# 18650_charge.net
KiCad netlist of a schematic drawn in Altium Designer
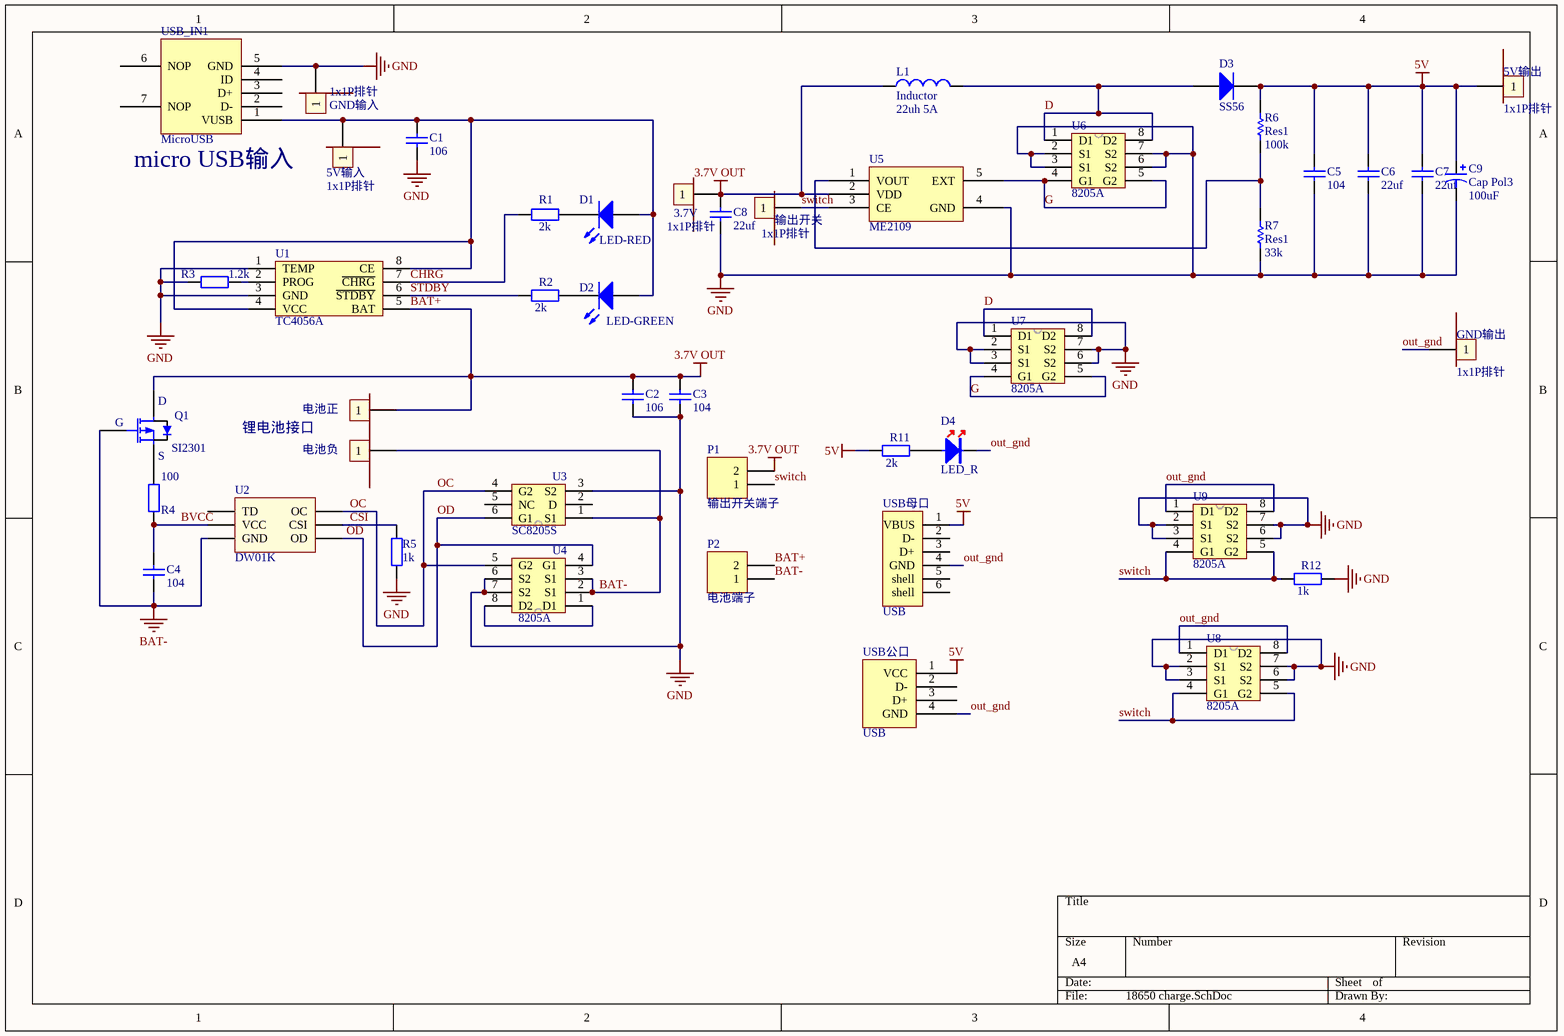
[diagram p0: 18650 charge.SchDoc]

(export (version "E")
  (design (tool "Eeschema 10.0.6"))
  (components
    (comp (ref "3.7V") (value "1x1P排针") (footprint "HDR1B") (libsource (lib "") (part "1x1P排针_1")))
    (comp (ref "5V输入") (value "1x1P排针") (footprint "HDR1B") (libsource (lib "") (part "1x1P排针_2")))
    (comp (ref "5V输出") (value "1x1P排针") (footprint "HDR1B") (libsource (lib "毕设锂电池充放电") (part "1x1P排针")))
    (comp (ref "C1") (value "106") (footprint "0805C") (libsource (lib "公司库2016") (part "0805电容")))
    (comp (ref "C2") (value "106") (footprint "0805C") (libsource (lib "公司库2016") (part "0805电容")))
    (comp (ref "C3") (value "104") (footprint "0805C") (libsource (lib "公司库2016") (part "0805电容")))
    (comp (ref "C4") (value "104") (footprint "0805C") (libsource (lib "公司库2016") (part "0805电容")))
    (comp (ref "C5") (value "104") (footprint "0805C") (libsource (lib "公司库2016") (part "0805电容")))
    (comp (ref "C6") (value "22uf") (footprint "0805C") (libsource (lib "公司库2016") (part "0805电容")))
    (comp (ref "C7") (value "22uf") (footprint "0805C") (libsource (lib "公司库2016") (part "0805电容")))
    (comp (ref "C8") (value "22uf") (footprint "0805C") (libsource (lib "公司库2016") (part "0805电容")))
    (comp (ref "C9")
      (value "Cap Pol3")
      (footprint "100uf youxin")
      (description "Polarized Capacitor (Surface Mount)")
      (fields (field (name "ALTIUM_VALUE") "100uF") (field (name "PUBLISHER") "Altium Limited"))
      (libsource (lib "Miscellaneous Devices") (part "Cap Pol3"))
    )
    (comp (ref "D1") (value "LED-RED") (footprint "0603LED") (libsource (lib "公司库2016") (part "0603LED")))
    (comp (ref "D2") (value "LED-GREEN") (footprint "0603LED") (libsource (lib "公司库2016") (part "0603LED")))
    (comp (ref "D3")
      (value "SS56")
      (footprint "SMC(DO-214AB)")
      (description "1 Amp General Purpose Rectifier")
      (fields (field (name "PUBLISHER") "Altium Limited"))
      (libsource (lib "Miscellaneous Devices") (part "Diode 1N4001"))
    )
    (comp (ref "D4") (value "LED_R") (footprint "6-0805_M") (libsource (lib "Diode二极管") (part "LED_R")))
    (comp (ref "GND输入") (value "1x1P排针") (footprint "HDR1B") (libsource (lib "") (part "1x1P排针_2")))
    (comp (ref "GND输出") (value "1x1P排针") (footprint "HDR1B") (libsource (lib "毕设锂电池充放电") (part "1x1P排针")))
    (comp (ref "L1")
      (value "Inductor")
      (footprint "L1110")
      (fields (field (name "ALTIUM_VALUE") "22uh 5A") (field (name "PUBLISHER") "Altium Limited"))
      (libsource (lib "Miscellaneous Devices") (part "Inductor"))
    )
    (comp (ref "P1")
      (value "输出开关端子")
      (footprint "KF301_2P")
      (description "Header, 2-Pin")
      (fields (field (name "PUBLISHER") "Altium Limited"))
      (libsource (lib "Miscellaneous Connectors") (part "Header 2"))
    )
    (comp (ref "P2")
      (value "电池端子")
      (footprint "KF301_2P")
      (description "Header, 2-Pin")
      (fields (field (name "PUBLISHER") "Altium Limited"))
      (libsource (lib "Miscellaneous Connectors") (part "Header 2"))
    )
    (comp (ref "Q1") (value "SI2301") (footprint "SOT23-3") (libsource (lib "公司库2016") (part "MOSP1")))
    (comp (ref "R1") (value "2k") (footprint "0603R") (libsource (lib "公司库2016") (part "0603电阻")))
    (comp (ref "R2") (value "2k") (footprint "0603R") (libsource (lib "公司库2016") (part "0603电阻")))
    (comp (ref "R3") (value "1.2k") (footprint "0603R") (libsource (lib "公司库2016") (part "0603电阻")))
    (comp (ref "R4") (value "100") (footprint "0603R") (libsource (lib "") (part "0603电阻_1")))
    (comp (ref "R5") (value "1k") (footprint "0603R") (libsource (lib "") (part "0603电阻_2")))
    (comp (ref "R6")
      (value "Res1")
      (footprint "6-0805_M")
      (description "Resistor")
      (fields (field (name "ALTIUM_VALUE") "100k") (field (name "PUBLISHER") "Altium Limited"))
      (libsource (lib "Miscellaneous Devices") (part "Res1"))
    )
    (comp (ref "R7")
      (value "Res1")
      (footprint "6-0805_M")
      (description "Resistor")
      (fields (field (name "ALTIUM_VALUE") "33k") (field (name "PUBLISHER") "Altium Limited"))
      (libsource (lib "Miscellaneous Devices") (part "Res1"))
    )
    (comp (ref "R11") (value "2k") (footprint "0603R") (libsource (lib "公司库2016") (part "0603电阻")))
    (comp (ref "R12") (value "1k") (footprint "0603R") (libsource (lib "公司库2016") (part "0603电阻")))
    (comp (ref "U1")
      (value "TC4056A")
      (footprint "SOIC8-MP1584EN")
      (description "SOP8D")
      (libsource (lib "公司库2016") (part "SC_ME4057"))
    )
    (comp (ref "U2") (value "DW01K") (footprint "sot23-6") (libsource (lib "公司库2016") (part "DW01")))
    (comp (ref "U3") (value "SC8205S") (footprint "sot23-6") (libsource (lib "公司库2016") (part "8205S")))
    (comp (ref "U4") (value "8205A") (footprint "Tssop8") (libsource (lib "") (part "8205A_1")))
    (comp (ref "U5") (value "ME2109") (footprint "SOT-23-5") (libsource (lib "ME2109") (part "ME2109")))
    (comp (ref "U6") (value "8205A") (footprint "Tssop8") (libsource (lib "公司库2016") (part "8205A")))
    (comp (ref "U7") (value "8205A") (footprint "Tssop8") (libsource (lib "公司库2016") (part "8205A")))
    (comp (ref "U8") (value "8205A") (footprint "Tssop8") (libsource (lib "公司库2016") (part "8205A")))
    (comp (ref "U9") (value "8205A") (footprint "Tssop8") (libsource (lib "公司库2016") (part "8205A")))
    (comp (ref "USB_IN1") (value "MicroUSB") (footprint "microusb") (libsource (lib "USB") (part "MicroUSB")))
    (comp (ref "USB公口") (value "USB") (footprint "USB-M-48") (libsource (lib "usb") (part "usb 公口")))
    (comp (ref "USB母口")
      (value "USB")
      (footprint "USB-A")
      (description "D")
      (libsource (lib "usb2") (part "USB"))
    )
    (comp (ref "电池正") (value "~") (footprint "HDR1B") (libsource (lib "公司库2016") (part "1x1P排针")))
    (comp (ref "电池负") (value "~") (footprint "HDR1B") (libsource (lib "公司库2016") (part "1x1P排针")))
    (comp (ref "输出开关") (value "1x1P排针") (footprint "HDR1B") (libsource (lib "") (part "1x1P排针_1")))
  )
  (nets
    (net (code "1") (name "/BVCC") (class "Default")
      (node (ref "C4") (pin "2") (pinfunction "2_2") (pintype "passive"))
      (node (ref "R4") (pin "2") (pinfunction "2_2") (pintype "passive"))
      (node (ref "U2") (pin "5") (pinfunction "VCC_5") (pintype "passive"))
    )
    (net (code "2") (name "/CHRG") (class "Default")
      (node (ref "R1") (pin "1") (pinfunction "1_1") (pintype "passive"))
      (node (ref "U1") (pin "7") (pinfunction "~{CHRG}_7") (pintype "passive"))
    )
    (net (code "3") (name "/CSI") (class "Default")
      (node (ref "R5") (pin "2") (pinfunction "2_2") (pintype "passive"))
      (node (ref "U2") (pin "2") (pinfunction "CSI_2") (pintype "passive"))
    )
    (net (code "4") (name "/D") (class "Default")
      (node (ref "D3") (pin "1") (pinfunction "A_1") (pintype "passive"))
      (node (ref "L1") (pin "2") (pinfunction "2_2") (pintype "passive"))
      (node (ref "U6") (pin "1") (pinfunction "D1_1") (pintype "passive"))
      (node (ref "U6") (pin "8") (pinfunction "D2_8") (pintype "passive"))
      (node (ref "U7") (pin "1") (pinfunction "D1_1") (pintype "passive"))
      (node (ref "U7") (pin "8") (pinfunction "D2_8") (pintype "passive"))
    )
    (net (code "5") (name "/G") (class "Default")
      (node (ref "U5") (pin "5") (pinfunction "EXT_5") (pintype "passive"))
      (node (ref "U6") (pin "4") (pinfunction "G1_4") (pintype "passive"))
      (node (ref "U6") (pin "5") (pinfunction "G2_5") (pintype "passive"))
      (node (ref "U7") (pin "4") (pinfunction "G1_4") (pintype "passive"))
      (node (ref "U7") (pin "5") (pinfunction "G2_5") (pintype "passive"))
    )
    (net (code "6") (name "/OC") (class "Default")
      (node (ref "U2") (pin "3") (pinfunction "OC_3") (pintype "passive"))
      (node (ref "U3") (pin "4") (pinfunction "G2_4") (pintype "passive"))
      (node (ref "U4") (pin "5") (pinfunction "G2_5") (pintype "passive"))
    )
    (net (code "7") (name "/OD") (class "Default")
      (node (ref "U2") (pin "1") (pinfunction "OD_1") (pintype "passive"))
      (node (ref "U3") (pin "6") (pinfunction "G1_6") (pintype "passive"))
      (node (ref "U4") (pin "4") (pinfunction "G1_4") (pintype "passive"))
    )
    (net (code "8") (name "/STDBY") (class "Default")
      (node (ref "R2") (pin "1") (pinfunction "1_1") (pintype "passive"))
      (node (ref "U1") (pin "6") (pinfunction "~{STDBY}_6") (pintype "passive"))
    )
    (net (code "9") (name "/out_gnd") (class "Default")
      (node (ref "D4") (pin "2") (pinfunction "2_2") (pintype "passive"))
      (node (ref "GND输出") (pin "1") (pinfunction "1_1") (pintype "passive"))
      (node (ref "U8") (pin "1") (pinfunction "D1_1") (pintype "passive"))
      (node (ref "U8") (pin "8") (pinfunction "D2_8") (pintype "passive"))
      (node (ref "U9") (pin "1") (pinfunction "D1_1") (pintype "passive"))
      (node (ref "U9") (pin "8") (pinfunction "D2_8") (pintype "passive"))
      (node (ref "USB公口") (pin "4") (pinfunction "GND_4") (pintype "passive"))
      (node (ref "USB母口") (pin "4") (pinfunction "GND_4") (pintype "passive"))
    )
    (net (code "10") (name "/switch") (class "Default")
      (node (ref "P1") (pin "1") (pinfunction "1_1") (pintype "passive"))
      (node (ref "R12") (pin "1") (pinfunction "1_1") (pintype "passive"))
      (node (ref "U5") (pin "3") (pinfunction "CE_3") (pintype "passive"))
      (node (ref "U8") (pin "4") (pinfunction "G1_4") (pintype "passive"))
      (node (ref "U8") (pin "5") (pinfunction "G2_5") (pintype "passive"))
      (node (ref "U9") (pin "4") (pinfunction "G1_4") (pintype "passive"))
      (node (ref "U9") (pin "5") (pinfunction "G2_5") (pintype "passive"))
      (node (ref "输出开关") (pin "1") (pinfunction "1_1") (pintype "passive"))
    )
    (net (code "11") (name "3.7V OUT") (class "Default")
      (node (ref "3.7V") (pin "1") (pinfunction "1_1") (pintype "passive"))
      (node (ref "C2") (pin "2") (pinfunction "2_2") (pintype "passive"))
      (node (ref "C3") (pin "2") (pinfunction "2_2") (pintype "passive"))
      (node (ref "C8") (pin "2") (pinfunction "2_2") (pintype "passive"))
      (node (ref "L1") (pin "1") (pinfunction "1_1") (pintype "passive"))
      (node (ref "P1") (pin "2") (pinfunction "2_2") (pintype "passive"))
      (node (ref "P2") (pin "2") (pinfunction "2_2") (pintype "passive"))
      (node (ref "Q1") (pin "3") (pinfunction "D_3") (pintype "passive"))
      (node (ref "U1") (pin "5") (pinfunction "BAT_5") (pintype "passive"))
      (node (ref "U5") (pin "2") (pinfunction "VDD_2") (pintype "passive"))
      (node (ref "电池正") (pin "1") (pinfunction "1_1") (pintype "passive"))
    )
    (net (code "12") (name "5V") (class "Default")
      (node (ref "5V输出") (pin "1") (pinfunction "1_1") (pintype "passive"))
      (node (ref "C5") (pin "2") (pinfunction "2_2") (pintype "passive"))
      (node (ref "C6") (pin "2") (pinfunction "2_2") (pintype "passive"))
      (node (ref "C7") (pin "2") (pinfunction "2_2") (pintype "passive"))
      (node (ref "C9") (pin "1") (pinfunction "1_1") (pintype "passive"))
      (node (ref "D3") (pin "2") (pinfunction "K_2") (pintype "passive"))
      (node (ref "R11") (pin "1") (pinfunction "1_1") (pintype "passive"))
      (node (ref "R6") (pin "2") (pinfunction "2_2") (pintype "passive"))
      (node (ref "USB公口") (pin "1") (pinfunction "VCC_1") (pintype "passive"))
      (node (ref "USB母口") (pin "1") (pinfunction "VBUS_1") (pintype "passive"))
    )
    (net (code "13") (name "BAT-") (class "Default")
      (node (ref "C4") (pin "1") (pinfunction "1_1") (pintype "passive"))
      (node (ref "P2") (pin "1") (pinfunction "1_1") (pintype "passive"))
      (node (ref "Q1") (pin "1") (pinfunction "G_1") (pintype "passive"))
      (node (ref "U2") (pin "6") (pinfunction "GND_6") (pintype "passive"))
      (node (ref "U3") (pin "1") (pinfunction "S1_1") (pintype "passive"))
      (node (ref "U4") (pin "2") (pinfunction "S1_2") (pintype "passive"))
      (node (ref "U4") (pin "3") (pinfunction "S1_3") (pintype "passive"))
      (node (ref "电池负") (pin "1") (pinfunction "1_1") (pintype "passive"))
    )
    (net (code "14") (name "GND") (class "Default")
      (node (ref "C1") (pin "1") (pinfunction "1_1") (pintype "passive"))
      (node (ref "C2") (pin "1") (pinfunction "1_1") (pintype "passive"))
      (node (ref "C3") (pin "1") (pinfunction "1_1") (pintype "passive"))
      (node (ref "C5") (pin "1") (pinfunction "1_1") (pintype "passive"))
      (node (ref "C6") (pin "1") (pinfunction "1_1") (pintype "passive"))
      (node (ref "C7") (pin "1") (pinfunction "1_1") (pintype "passive"))
      (node (ref "C8") (pin "1") (pinfunction "1_1") (pintype "passive"))
      (node (ref "C9") (pin "2") (pinfunction "2_2") (pintype "passive"))
      (node (ref "GND输入") (pin "1") (pinfunction "1_1") (pintype "passive"))
      (node (ref "R12") (pin "2") (pinfunction "2_2") (pintype "passive"))
      (node (ref "R3") (pin "1") (pinfunction "1_1") (pintype "passive"))
      (node (ref "R5") (pin "1") (pinfunction "1_1") (pintype "passive"))
      (node (ref "R7") (pin "1") (pinfunction "1_1") (pintype "passive"))
      (node (ref "U1") (pin "1") (pinfunction "TEMP_1") (pintype "passive"))
      (node (ref "U1") (pin "3") (pinfunction "GND_3") (pintype "passive"))
      (node (ref "U3") (pin "3") (pinfunction "S2_3") (pintype "passive"))
      (node (ref "U4") (pin "6") (pinfunction "S2_6") (pintype "passive"))
      (node (ref "U4") (pin "7") (pinfunction "S2_7") (pintype "passive"))
      (node (ref "U5") (pin "4") (pinfunction "GND_4") (pintype "passive"))
      (node (ref "U6") (pin "2") (pinfunction "S1_2") (pintype "passive"))
      (node (ref "U6") (pin "3") (pinfunction "S1_3") (pintype "passive"))
      (node (ref "U6") (pin "6") (pinfunction "S2_6") (pintype "passive"))
      (node (ref "U6") (pin "7") (pinfunction "S2_7") (pintype "passive"))
      (node (ref "U7") (pin "2") (pinfunction "S1_2") (pintype "passive"))
      (node (ref "U7") (pin "3") (pinfunction "S1_3") (pintype "passive"))
      (node (ref "U7") (pin "6") (pinfunction "S2_6") (pintype "passive"))
      (node (ref "U7") (pin "7") (pinfunction "S2_7") (pintype "passive"))
      (node (ref "U8") (pin "2") (pinfunction "S1_2") (pintype "passive"))
      (node (ref "U8") (pin "3") (pinfunction "S1_3") (pintype "passive"))
      (node (ref "U8") (pin "6") (pinfunction "S2_6") (pintype "passive"))
      (node (ref "U8") (pin "7") (pinfunction "S2_7") (pintype "passive"))
      (node (ref "U9") (pin "2") (pinfunction "S1_2") (pintype "passive"))
      (node (ref "U9") (pin "3") (pinfunction "S1_3") (pintype "passive"))
      (node (ref "U9") (pin "6") (pinfunction "S2_6") (pintype "passive"))
      (node (ref "U9") (pin "7") (pinfunction "S2_7") (pintype "passive"))
      (node (ref "USB_IN1") (pin "5") (pinfunction "GND_5") (pintype "passive"))
    )
    (net (code "15") (name "Net-(D1-PadK)") (class "Default")
      (node (ref "D1") (pin "K") (pinfunction "K_K") (pintype "passive"))
      (node (ref "R1") (pin "2") (pinfunction "2_2") (pintype "passive"))
    )
    (net (code "16") (name "Net-(D2-PadK)") (class "Default")
      (node (ref "D2") (pin "K") (pinfunction "K_K") (pintype "passive"))
      (node (ref "R2") (pin "2") (pinfunction "2_2") (pintype "passive"))
    )
    (net (code "17") (name "Net-(D4-Pad1)") (class "Default")
      (node (ref "D4") (pin "1") (pinfunction "1_1") (pintype "passive"))
      (node (ref "R11") (pin "2") (pinfunction "2_2") (pintype "passive"))
    )
    (net (code "18") (name "Net-(Q1-S)") (class "Default")
      (node (ref "Q1") (pin "2") (pinfunction "S_2") (pintype "passive"))
      (node (ref "R4") (pin "1") (pinfunction "1_1") (pintype "passive"))
    )
    (net (code "19") (name "Net-(U1-CE)") (class "Default")
      (node (ref "5V输入") (pin "1") (pinfunction "1_1") (pintype "passive"))
      (node (ref "C1") (pin "2") (pinfunction "2_2") (pintype "passive"))
      (node (ref "D1") (pin "A") (pinfunction "A_A") (pintype "passive"))
      (node (ref "D2") (pin "A") (pinfunction "A_A") (pintype "passive"))
      (node (ref "U1") (pin "4") (pinfunction "VCC_4") (pintype "passive"))
      (node (ref "U1") (pin "8") (pinfunction "CE_8") (pintype "passive"))
      (node (ref "USB_IN1") (pin "1") (pinfunction "VUSB_1") (pintype "passive"))
    )
    (net (code "20") (name "Net-(U1-PROG)") (class "Default")
      (node (ref "R3") (pin "2") (pinfunction "2_2") (pintype "passive"))
      (node (ref "U1") (pin "2") (pinfunction "PROG_2") (pintype "passive"))
    )
    (net (code "21") (name "Net-(U4-D1)") (class "Default")
      (node (ref "U4") (pin "1") (pinfunction "D1_1") (pintype "passive"))
      (node (ref "U4") (pin "8") (pinfunction "D2_8") (pintype "passive"))
    )
    (net (code "22") (name "Net-(U5-VOUT)") (class "Default")
      (node (ref "R6") (pin "1") (pinfunction "1_1") (pintype "passive"))
      (node (ref "R7") (pin "2") (pinfunction "2_2") (pintype "passive"))
      (node (ref "U5") (pin "1") (pinfunction "VOUT_1") (pintype "passive"))
    )
    (net (code "23") (name "unconnected-(U2-TD-Pad4)") (class "Default")
      (node (ref "U2") (pin "4") (pinfunction "TD_4") (pintype "passive"))
    )
    (net (code "24") (name "unconnected-(U3-D-Pad2)") (class "Default")
      (node (ref "U3") (pin "2") (pinfunction "D_2") (pintype "passive"))
    )
    (net (code "25") (name "unconnected-(U3-NC-Pad5)") (class "Default")
      (node (ref "U3") (pin "5") (pinfunction "NC_5") (pintype "passive"))
    )
    (net (code "26") (name "unconnected-(USB_IN1-D+-Pad3)") (class "Default")
      (node (ref "USB_IN1") (pin "3") (pinfunction "D+_3") (pintype "passive"))
    )
    (net (code "27") (name "unconnected-(USB_IN1-D--Pad2)") (class "Default")
      (node (ref "USB_IN1") (pin "2") (pinfunction "D-_2") (pintype "passive"))
    )
    (net (code "28") (name "unconnected-(USB_IN1-ID-Pad4)") (class "Default")
      (node (ref "USB_IN1") (pin "4") (pinfunction "ID_4") (pintype "passive"))
    )
    (net (code "29") (name "unconnected-(USB_IN1-NOP-Pad6)") (class "Default")
      (node (ref "USB_IN1") (pin "6") (pinfunction "NOP_6") (pintype "passive"))
    )
    (net (code "30") (name "unconnected-(USB_IN1-NOP-Pad7)") (class "Default")
      (node (ref "USB_IN1") (pin "7") (pinfunction "NOP_7") (pintype "passive"))
    )
    (net (code "31") (name "unconnected-(USB公口-D+-Pad3)") (class "Default")
      (node (ref "USB公口") (pin "3") (pinfunction "D+_3") (pintype "passive"))
    )
    (net (code "32") (name "unconnected-(USB公口-D--Pad2)") (class "Default")
      (node (ref "USB公口") (pin "2") (pinfunction "D-_2") (pintype "passive"))
    )
    (net (code "33") (name "unconnected-(USB母口-D+-Pad3)") (class "Default")
      (node (ref "USB母口") (pin "3") (pinfunction "D+_3") (pintype "passive"))
    )
    (net (code "34") (name "unconnected-(USB母口-D--Pad2)") (class "Default")
      (node (ref "USB母口") (pin "2") (pinfunction "D-_2") (pintype "passive"))
    )
    (net (code "35") (name "unconnected-(USB母口-shell-Pad5)") (class "Default")
      (node (ref "USB母口") (pin "5") (pinfunction "shell_5") (pintype "passive"))
    )
    (net (code "36") (name "unconnected-(USB母口-shell-Pad6)") (class "Default")
      (node (ref "USB母口") (pin "6") (pinfunction "shell_6") (pintype "passive"))
    )
  )
)
